# MC50_BLE.net
KiCad netlist of a schematic drawn in Altium Designer
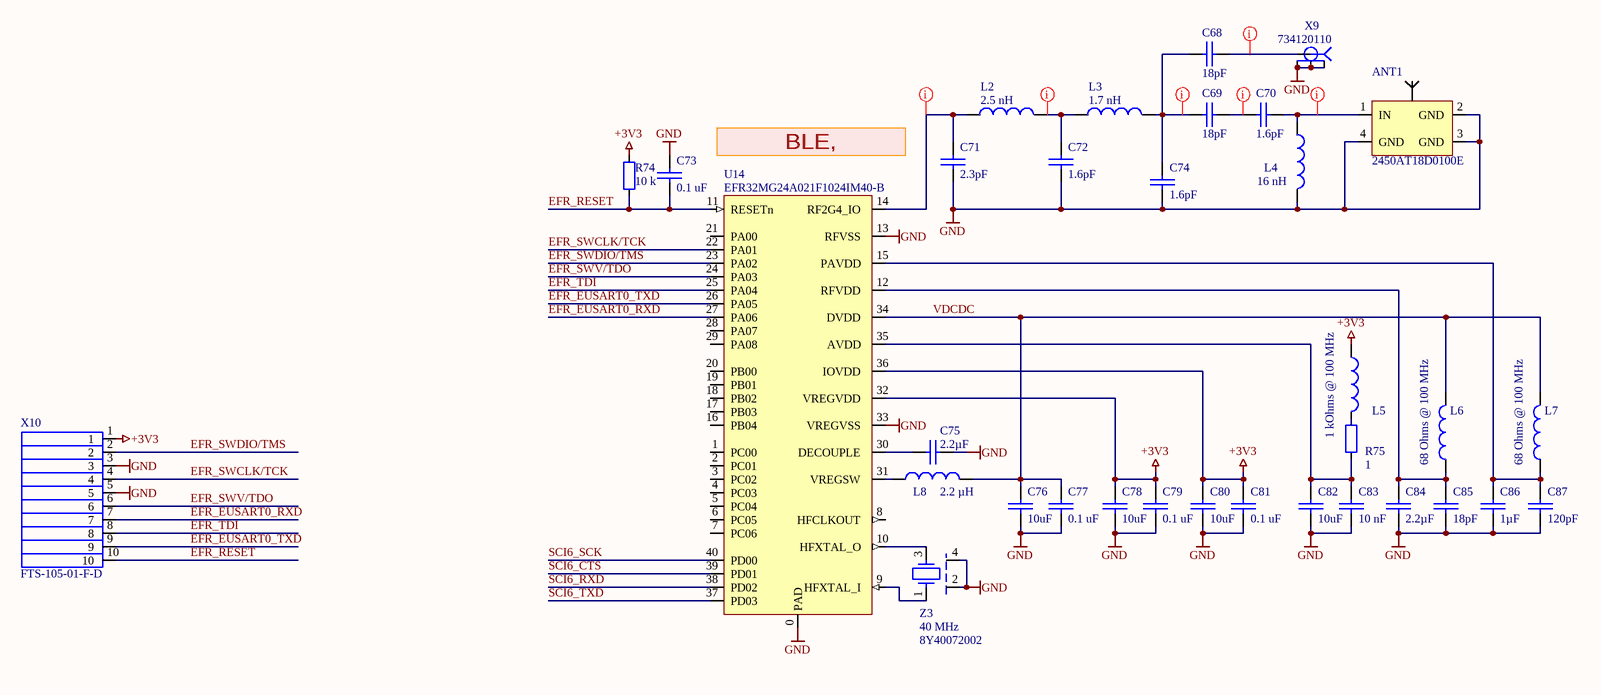
[diagram p0: MC50_BLE.SchDoc]

(export (version "E")
  (design (tool "Eeschema 10.0.6"))
  (components
    (comp (ref "ANT1")
      (value "2450AT18D0100E")
      (footprint "2450AT18D0100E_JOT")
      (description "2.4GHz Chip RF Antenna 2.4GHz ~ 2.5GHz 1.5dBi Solder Surface Mount")
      (fields
        (field (name "PARTNUM") "712-1573-1-ND")
        (field (name "MANUFACTURER") "Johanson Technology Inc.")
      )
      (libsource (lib "ea_Antennas") (part "2450AT18D0100E"))
    )
    (comp (ref "C68")
      (value "18pF")
      (footprint "0402 CAP")
      (description "18pF, ±5%, 50V, C0G, NP0, 0402 (1005 Metric), -55°C ~ 125°C, -, General Purpose")
      (fields (field (name "PART NUMBER") "CC0402JRNPO9BN180") (field (name "MANUFACTURER") "Yageo"))
      (libsource (lib "ea_PassivComps") (part "Capacitor"))
    )
    (comp (ref "C69")
      (value "18pF")
      (footprint "0402 CAP")
      (description "18pF, ±5%, 50V, C0G, NP0, 0402 (1005 Metric), -55°C ~ 125°C, -, General Purpose")
      (fields (field (name "PART NUMBER") "CC0402JRNPO9BN180") (field (name "MANUFACTURER") "Yageo"))
      (libsource (lib "ea_PassivComps") (part "Capacitor"))
    )
    (comp (ref "C70")
      (value "1.6pF")
      (footprint "0402 CAP")
      (description "1.6pF, ±0.1pF, 50V, C0G, NP0, 0402 (1005 Metric), -55°C ~ 125°C, -, General Purpose")
      (fields (field (name "PART NUMBER") "CC0402BRNPO9BN1R6") (field (name "MANUFACTURER") "Yageo"))
      (libsource (lib "ea_PassivComps") (part "Capacitor"))
    )
    (comp (ref "C71")
      (value "2.3pF")
      (footprint "0402 CAP")
      (description "2.3pF, ±0.05pF, 50V, C0G, NP0, 0402 (1005 Metric), -55°C ~ 125°C, -, RF, Microwave, High Frequency")
      (fields
        (field (name "PART NUMBER") "885392005009")
        (field (name "MANUFACTURER") "Wurth Electronics Inc.")
      )
      (libsource (lib "ea_PassivComps") (part "Capacitor"))
    )
    (comp (ref "C72")
      (value "1.6pF")
      (footprint "0402 CAP")
      (description "1.6pF, ±0.1pF, 50V, C0G, NP0, 0402 (1005 Metric), -55°C ~ 125°C, -, General Purpose")
      (fields (field (name "PART NUMBER") "CC0402BRNPO9BN1R6") (field (name "MANUFACTURER") "Yageo"))
      (libsource (lib "ea_PassivComps") (part "Capacitor"))
    )
    (comp (ref "C73")
      (value "0.1 uF")
      (footprint "1608[0603]")
      (description "0.1 µF ±10% 50V Ceramic Capacitor X7R 0603 (1608 Metric),  \r\n-55°C ~ 125°C")
      (fields
        (field (name "TOLERANCE") "+-10%")
        (field (name "MANUFACTURER") "Walsin Technology Corporation")
      )
      (libsource (lib "ea_Capacitors_0603") (part "0603B104K500CT"))
    )
    (comp (ref "C74")
      (value "1.6pF")
      (footprint "0402 CAP")
      (description "1.6pF, ±0.1pF, 50V, C0G, NP0, 0402 (1005 Metric), -55°C ~ 125°C, -, General Purpose")
      (fields (field (name "PART NUMBER") "CC0402BRNPO9BN1R6") (field (name "MANUFACTURER") "Yageo"))
      (libsource (lib "ea_PassivComps") (part "Capacitor"))
    )
    (comp (ref "C75")
      (value "2.2µF")
      (footprint "0603 CAP")
      (description "2.2µF, ±10%, 10V, X7R, 0603 (1608 Metric), -55°C ~ 125°C, -, General Purpose")
      (fields
        (field (name "PART NUMBER") "GRM188R71A225KE15D")
        (field (name "MANUFACTURER") "Murata Electronics North America")
      )
      (libsource (lib "ea_PassivComps") (part "Capacitor"))
    )
    (comp (ref "C76")
      (value "10uF")
      (footprint "1608[0603]")
      (description "10 µF ±10% 25V Ceramic Capacitor X5R 0603 (1608 Metric), -55°C ~ 85°C")
      (fields (field (name "MANUFACTURER") "Murata Electronics") (field (name "TOLERANCE") "±10%"))
      (libsource (lib "ea_Capacitors_0603") (part "GRM188R61E106KA73D"))
    )
    (comp (ref "C77")
      (value "0.1 uF")
      (footprint "1608[0603]")
      (description "0.1 µF ±10% 50V Ceramic Capacitor X7R 0603 (1608 Metric),  \r\n-55°C ~ 125°C")
      (fields
        (field (name "TOLERANCE") "+-10%")
        (field (name "MANUFACTURER") "Walsin Technology Corporation")
      )
      (libsource (lib "ea_Capacitors_0603") (part "0603B104K500CT"))
    )
    (comp (ref "C78")
      (value "10uF")
      (footprint "1608[0603]")
      (description "10 µF ±10% 25V Ceramic Capacitor X5R 0603 (1608 Metric), -55°C ~ 85°C")
      (fields (field (name "MANUFACTURER") "Murata Electronics") (field (name "TOLERANCE") "±10%"))
      (libsource (lib "ea_Capacitors_0603") (part "GRM188R61E106KA73D"))
    )
    (comp (ref "C79")
      (value "0.1 uF")
      (footprint "1608[0603]")
      (description "0.1 µF ±10% 50V Ceramic Capacitor X7R 0603 (1608 Metric),  \r\n-55°C ~ 125°C")
      (fields
        (field (name "TOLERANCE") "+-10%")
        (field (name "MANUFACTURER") "Walsin Technology Corporation")
      )
      (libsource (lib "ea_Capacitors_0603") (part "0603B104K500CT"))
    )
    (comp (ref "C80")
      (value "10uF")
      (footprint "1608[0603]")
      (description "10 µF ±10% 25V Ceramic Capacitor X5R 0603 (1608 Metric), -55°C ~ 85°C")
      (fields (field (name "MANUFACTURER") "Murata Electronics") (field (name "TOLERANCE") "±10%"))
      (libsource (lib "ea_Capacitors_0603") (part "GRM188R61E106KA73D"))
    )
    (comp (ref "C81")
      (value "0.1 uF")
      (footprint "1608[0603]")
      (description "0.1 µF ±10% 50V Ceramic Capacitor X7R 0603 (1608 Metric),  \r\n-55°C ~ 125°C")
      (fields
        (field (name "TOLERANCE") "+-10%")
        (field (name "MANUFACTURER") "Walsin Technology Corporation")
      )
      (libsource (lib "ea_Capacitors_0603") (part "0603B104K500CT"))
    )
    (comp (ref "C82")
      (value "10uF")
      (footprint "1608[0603]")
      (description "10 µF ±10% 25V Ceramic Capacitor X5R 0603 (1608 Metric), -55°C ~ 85°C")
      (fields (field (name "MANUFACTURER") "Murata Electronics") (field (name "TOLERANCE") "±10%"))
      (libsource (lib "ea_Capacitors_0603") (part "GRM188R61E106KA73D"))
    )
    (comp (ref "C83")
      (value "10 nF")
      (footprint "0603 CAP")
      (description "10000pF, ±5%, 50V, C0G, NP0, 0603 (1608 Metric), -55°C ~ 125°C, Low ESL, General Purpose")
      (fields
        (field (name "PART NUMBER") "C1608C0G1H103J080AA")
        (field (name "MANUFACTURER") "TDK Corporation")
      )
      (libsource (lib "ea_PassivComps") (part "Capacitor"))
    )
    (comp (ref "C84")
      (value "2.2µF")
      (footprint "0603 CAP")
      (description "2.2µF, ±10%, 10V, X7R, 0603 (1608 Metric), -55°C ~ 125°C, -, General Purpose")
      (fields
        (field (name "PART NUMBER") "GRM188R71A225KE15D")
        (field (name "MANUFACTURER") "Murata Electronics North America")
      )
      (libsource (lib "ea_PassivComps") (part "Capacitor"))
    )
    (comp (ref "C85")
      (value "18pF")
      (footprint "0603 CAP")
      (description "18pF, ±10%, 50V, C0G, NP0, 0603 (1608 Metric), -55°C ~ 125°C, Low ESL, General Purpose")
      (fields (field (name "PART NUMBER") "C0603C180K5GACTU") (field (name "MANUFACTURER") "KEMET"))
      (libsource (lib "ea_PassivComps") (part "Capacitor"))
    )
    (comp (ref "C86")
      (value "1µF")
      (footprint "0603 CAP")
      (description "1µF, ±10%, 50V, X5R, 0603 (1608 Metric), -55°C ~ 85°C, -, General Purpose")
      (fields
        (field (name "PART NUMBER") "CL10A105KB8NNNC")
        (field (name "MANUFACTURER") "Samsung Electro-Mechanics")
      )
      (libsource (lib "ea_PassivComps") (part "Capacitor"))
    )
    (comp (ref "C87")
      (value "120pF")
      (footprint "0603 CAP")
      (description "120pF, ±5%, 50V, C0G, NP0, 0603 (1608 Metric), -55°C ~ 125°C, -, General Purpose")
      (fields
        (field (name "PART NUMBER") "CL10C121JB8NCNC")
        (field (name "MANUFACTURER") "Samsung Electro-Mechanics")
      )
      (libsource (lib "ea_PassivComps") (part "Capacitor"))
    )
    (comp (ref "L2")
      (value "2.5 nH")
      (footprint "INDC1005-0402")
      (description "2.5 nH Unshielded Thin Film Inductor 440 mA 350mOhm Max 0402 (1005 Metric)")
      (fields (field (name "MANUFACTURER") "Abracon LLC") (field (name "TOLERANCE") "±0.1nH"))
      (libsource (lib "ea_RF_inductors") (part "ATFC-0402-2N5B-T"))
    )
    (comp (ref "L3")
      (value "1.7 nH")
      (footprint "INDC1005-0402")
      (description "1.7 nH Unshielded Thin Film Inductor 560 mA 250mOhm Max 0402 (1005 Metric)")
      (fields (field (name "MANUFACTURER") "Abracon LLC") (field (name "TOLERANCE") "±0.1nH"))
      (libsource (lib "ea_RF_inductors") (part "ATFC-0402-1N7B-T"))
    )
    (comp (ref "L4")
      (value "16 nH")
      (footprint "INDC1005-0402")
      (description "16 nH Unshielded Drum Core, Wirewound Inductor 850 mA 130mOhm 0402 (1005 Metric)")
      (fields (field (name "MANUFACTURER") "Delta Electronics/Components") (field (name "TOLERANCE") "5%"))
      (libsource (lib "ea_RF_inductors") (part "0402HP-160EJTS"))
    )
    (comp (ref "L5")
      (value "1 kOhms @ 100 MHz")
      (footprint "0603")
      (description "1 kOhms @ 100 MHz 1 Power, Signal Line Ferrite Bead 0603 (1608 Metric) 200mA 600mOhm")
      (fields
        (field (name "MANUFACTURER") "Laird-Signal Integrity Products")
        (field (name "PARTNUM") "240-2378-1-ND")
      )
      (libsource (lib "ea_Inductors") (part "HZ0603B102R-10"))
    )
    (comp (ref "L6")
      (value "68 Ohms @ 100 MHz")
      (footprint "0603")
      (description "68 Ohms @ 100 MHz 1 Ferrite Bead 0603 (1608 Metric) 200mA 100mOhm, -55°C ~ 125°C")
      (fields (field (name "MANUFACTURER") "Murata Manufacturing") (field (name "PARTNUM") "541-2605-1-ND"))
      (libsource (lib "ea_Inductors") (part "ILBB0603ER680V"))
    )
    (comp (ref "L7")
      (value "68 Ohms @ 100 MHz")
      (footprint "0603")
      (description "68 Ohms @ 100 MHz 1 Ferrite Bead 0603 (1608 Metric) 200mA 100mOhm, -55°C ~ 125°C")
      (fields (field (name "MANUFACTURER") "Murata Manufacturing") (field (name "PARTNUM") "541-2605-1-ND"))
      (libsource (lib "ea_Inductors") (part "ILBB0603ER680V"))
    )
    (comp (ref "L8")
      (value "2.2 µH")
      (footprint "0603")
      (description "2.2 µH Shielded Multilayer Inductor 700 mA 470mOhm Max 0603 (1608 Metric)")
      (fields (field (name "MANUFACTURER") "Murata Electronics") (field (name "PARTNUM") "490-15982-1-ND"))
      (libsource (lib "ea_Inductors") (part "LQM18PZ2R2MFHD"))
    )
    (comp (ref "R74")
      (value "10 k")
      (footprint "0603")
      (fields
        (field (name "MANUFACTURER") "Bourns Inc.")
        (field (name "TOLERANCE") "±1%")
        (field (name "VOLTAGE") "75V")
      )
      (libsource (lib "") (part "Resistor_1"))
    )
    (comp (ref "R75")
      (value "1")
      (footprint "0603")
      (description "1 Ohms, ±1%, 0.1W, 1/10W, Thick Film, ±100ppm/°C, 0603 (1608 Metric), -55°C ~ 155°C, -")
      (fields (field (name "MANUFACTURER") "Vishay Dale") (field (name "TOLERANCE") "±1%"))
      (libsource (lib "ea_PassivComps") (part "Resistor"))
    )
    (comp (ref "U14")
      (value "EFR32MG24A021F1024IM40-B")
      (footprint "QFN40 Silabs")
      (fields
        (field (name "MANUFACTURER") "Silicon Labs")
        (field (name "PARTNUM") "336-EFR32MG24A021F1024IM40-B-ND")
      )
      (libsource (lib "ea_IC_RF") (part "EFR32MG24A021F1024IM40-B"))
    )
    (comp (ref "X9")
      (value "734120110")
      (footprint "0734120110")
      (description "U.FL (UMCC) Connector Receptacle, Male Pin 50 Ohm Surface Mount Solder")
      (fields (field (name "MANUFACTURER") "Molex") (field (name "PARTNUM") "WM5587TR-ND"))
      (libsource (lib "ea_Connectors_RF") (part "0734120110"))
    )
    (comp (ref "X10")
      (value "FTS-105-01-F-D")
      (footprint "FTS-105-01-F-D")
      (description "Board-To-Board Connector, Vertical, FTS Series, Through Hole, Header, 10, 1.27 mm")
      (fields (field (name "MANUFACTURER") "SAMTEC") (field (name "PARTNUM") "1928242"))
      (libsource (lib "ea_JTAG_SWD") (part "FTS-105-01-F-D"))
    )
    (comp (ref "Z3")
      (value "8Y40072002")
      (footprint "4-SMD 2.00mm x 1.60mm")
      (description "40 MHz Crystal 8pF 80 Ohms 4-SMD, No Lead, -20°C ~ 70°C")
      (fields
        (field (name "MANUFACTURER") "TXC CORPORATION")
        (field (name "PARTNUM") "887-8Y40072002CT-ND")
        (field (name "ALTIUM_VALUE") "40 MHz")
      )
      (libsource (lib "ea_OSC_CLK_GEN") (part "8Y40072002"))
    )
  )
  (nets
    (net (code "1") (name "+3V3") (class "Default")
      (node (ref "C78") (pin "1") (pinfunction "1_1") (pintype "passive"))
      (node (ref "C79") (pin "2") (pinfunction "2_2") (pintype "passive"))
      (node (ref "C80") (pin "1") (pinfunction "1_1") (pintype "passive"))
      (node (ref "C81") (pin "2") (pinfunction "2_2") (pintype "passive"))
      (node (ref "L5") (pin "1") (pinfunction "1_1") (pintype "passive"))
      (node (ref "R74") (pin "1") (pinfunction "1_1") (pintype "passive"))
      (node (ref "U14") (pin "32") (pinfunction "VREGVDD_32") (pintype "power_in"))
      (node (ref "U14") (pin "36") (pinfunction "IOVDD_36") (pintype "power_in"))
      (node (ref "X10") (pin "1") (pinfunction "1_1") (pintype "passive"))
    )
    (net (code "2") (name "/EFR_EUSART0_RXD") (class "Default")
      (node (ref "U14") (pin "27") (pinfunction "PA06_27") (pintype "bidirectional"))
      (node (ref "X10") (pin "7") (pinfunction "7_7") (pintype "power_in"))
    )
    (net (code "3") (name "/EFR_EUSART0_TXD") (class "Default")
      (node (ref "U14") (pin "26") (pinfunction "PA05_26") (pintype "bidirectional"))
      (node (ref "X10") (pin "9") (pinfunction "9_9") (pintype "power_in"))
    )
    (net (code "4") (name "/EFR_RESET") (class "Default")
      (node (ref "C73") (pin "1") (pinfunction "1_1") (pintype "passive"))
      (node (ref "R74") (pin "2") (pinfunction "2_2") (pintype "passive"))
      (node (ref "U14") (pin "11") (pinfunction "RESETn_11") (pintype "input"))
      (node (ref "X10") (pin "10") (pinfunction "10_10") (pintype "power_in"))
    )
    (net (code "5") (name "/EFR_SWCLK{slash}TCK") (class "Default")
      (node (ref "U14") (pin "22") (pinfunction "PA01_22") (pintype "bidirectional"))
      (node (ref "X10") (pin "4") (pinfunction "4_4") (pintype "passive"))
    )
    (net (code "6") (name "/EFR_SWDIO{slash}TMS") (class "Default")
      (node (ref "U14") (pin "23") (pinfunction "PA02_23") (pintype "bidirectional"))
      (node (ref "X10") (pin "2") (pinfunction "2_2") (pintype "passive"))
    )
    (net (code "7") (name "/EFR_SWV{slash}TDO") (class "Default")
      (node (ref "U14") (pin "24") (pinfunction "PA03_24") (pintype "bidirectional"))
      (node (ref "X10") (pin "6") (pinfunction "6_6") (pintype "power_in"))
    )
    (net (code "8") (name "/EFR_TDI") (class "Default")
      (node (ref "U14") (pin "25") (pinfunction "PA04_25") (pintype "bidirectional"))
      (node (ref "X10") (pin "8") (pinfunction "8_8") (pintype "power_in"))
    )
    (net (code "9") (name "/SCI6_CTS") (class "Default")
      (node (ref "U14") (pin "39") (pinfunction "PD01_39") (pintype "bidirectional"))
    )
    (net (code "10") (name "/SCI6_RXD") (class "Default")
      (node (ref "U14") (pin "38") (pinfunction "PD02_38") (pintype "bidirectional"))
    )
    (net (code "11") (name "/SCI6_SCK") (class "Default")
      (node (ref "U14") (pin "40") (pinfunction "PD00_40") (pintype "bidirectional"))
    )
    (net (code "12") (name "/SCI6_TXD") (class "Default")
      (node (ref "U14") (pin "37") (pinfunction "PD03_37") (pintype "bidirectional"))
    )
    (net (code "13") (name "/VDCDC") (class "Default")
      (node (ref "C76") (pin "1") (pinfunction "1_1") (pintype "passive"))
      (node (ref "C77") (pin "2") (pinfunction "2_2") (pintype "passive"))
      (node (ref "L6") (pin "2") (pinfunction "2_2") (pintype "passive"))
      (node (ref "L7") (pin "2") (pinfunction "2_2") (pintype "passive"))
      (node (ref "L8") (pin "2") (pinfunction "2_2") (pintype "passive"))
      (node (ref "U14") (pin "34") (pinfunction "DVDD_34") (pintype "power_in"))
    )
    (net (code "14") (name "GND") (class "Default")
      (node (ref "ANT1") (pin "2") (pinfunction "GND_2") (pintype "passive"))
      (node (ref "ANT1") (pin "3") (pinfunction "GND_3") (pintype "passive"))
      (node (ref "ANT1") (pin "4") (pinfunction "GND_4") (pintype "passive"))
      (node (ref "C71") (pin "2") (pinfunction "2_2") (pintype "passive"))
      (node (ref "C72") (pin "2") (pinfunction "2_2") (pintype "passive"))
      (node (ref "C73") (pin "2") (pinfunction "2_2") (pintype "passive"))
      (node (ref "C74") (pin "2") (pinfunction "2_2") (pintype "passive"))
      (node (ref "C75") (pin "2") (pinfunction "2_2") (pintype "passive"))
      (node (ref "C76") (pin "2") (pinfunction "2_2") (pintype "passive"))
      (node (ref "C77") (pin "1") (pinfunction "1_1") (pintype "passive"))
      (node (ref "C78") (pin "2") (pinfunction "2_2") (pintype "passive"))
      (node (ref "C79") (pin "1") (pinfunction "1_1") (pintype "passive"))
      (node (ref "C80") (pin "2") (pinfunction "2_2") (pintype "passive"))
      (node (ref "C81") (pin "1") (pinfunction "1_1") (pintype "passive"))
      (node (ref "C82") (pin "2") (pinfunction "2_2") (pintype "passive"))
      (node (ref "C83") (pin "2") (pinfunction "2_2") (pintype "passive"))
      (node (ref "C84") (pin "1") (pinfunction "1_1") (pintype "passive"))
      (node (ref "C85") (pin "2") (pinfunction "2_2") (pintype "passive"))
      (node (ref "C86") (pin "2") (pinfunction "2_2") (pintype "passive"))
      (node (ref "C87") (pin "2") (pinfunction "2_2") (pintype "passive"))
      (node (ref "L4") (pin "2") (pinfunction "2_2") (pintype "passive"))
      (node (ref "U14") (pin "0") (pinfunction "PAD_0") (pintype "power_in"))
      (node (ref "U14") (pin "13") (pinfunction "RFVSS_13") (pintype "power_in"))
      (node (ref "U14") (pin "33") (pinfunction "VREGVSS_33") (pintype "power_in"))
      (node (ref "X10") (pin "3") (pinfunction "3_3") (pintype "passive"))
      (node (ref "X10") (pin "5") (pinfunction "5_5") (pintype "power_in"))
      (node (ref "X9") (pin "2") (pinfunction "2_2") (pintype "passive"))
      (node (ref "X9") (pin "3") (pinfunction "3_3") (pintype "passive"))
      (node (ref "X9") (pin "4") (pinfunction "3_4") (pintype "passive"))
      (node (ref "Z3") (pin "2") (pinfunction "2_2") (pintype "passive"))
      (node (ref "Z3") (pin "4") (pinfunction "4_4") (pintype "passive"))
    )
    (net (code "15") (name "Net-(ANT1-IN)") (class "Default")
      (node (ref "ANT1") (pin "1") (pinfunction "IN_1") (pintype "passive"))
      (node (ref "C70") (pin "2") (pinfunction "2_2") (pintype "passive"))
      (node (ref "L4") (pin "1") (pinfunction "1_1") (pintype "passive"))
    )
    (net (code "16") (name "Net-(C68-Pad1)") (class "Default")
      (node (ref "C68") (pin "1") (pinfunction "1_1") (pintype "passive"))
      (node (ref "C69") (pin "1") (pinfunction "1_1") (pintype "passive"))
      (node (ref "C74") (pin "1") (pinfunction "1_1") (pintype "passive"))
      (node (ref "L3") (pin "2") (pinfunction "2_2") (pintype "passive"))
    )
    (net (code "17") (name "Net-(C69-Pad2)") (class "Default")
      (node (ref "C69") (pin "2") (pinfunction "2_2") (pintype "passive"))
      (node (ref "C70") (pin "1") (pinfunction "1_1") (pintype "passive"))
    )
    (net (code "18") (name "Net-(C72-Pad1)") (class "Default")
      (node (ref "C72") (pin "1") (pinfunction "1_1") (pintype "passive"))
      (node (ref "L2") (pin "2") (pinfunction "2_2") (pintype "passive"))
      (node (ref "L3") (pin "1") (pinfunction "1_1") (pintype "passive"))
    )
    (net (code "19") (name "Net-(L5-Pad2)") (class "Default")
      (node (ref "L5") (pin "2") (pinfunction "2_2") (pintype "passive"))
      (node (ref "R75") (pin "2") (pinfunction "2_2") (pintype "passive"))
    )
    (net (code "20") (name "Net-(U14-AVDD)") (class "Default")
      (node (ref "C82") (pin "1") (pinfunction "1_1") (pintype "passive"))
      (node (ref "C83") (pin "1") (pinfunction "1_1") (pintype "passive"))
      (node (ref "R75") (pin "1") (pinfunction "1_1") (pintype "passive"))
      (node (ref "U14") (pin "35") (pinfunction "AVDD_35") (pintype "power_in"))
    )
    (net (code "21") (name "Net-(U14-DECOUPLE)") (class "Default")
      (node (ref "C75") (pin "1") (pinfunction "1_1") (pintype "passive"))
      (node (ref "U14") (pin "30") (pinfunction "DECOUPLE_30") (pintype "bidirectional"))
    )
    (net (code "22") (name "Net-(U14-HFXTAL_I)") (class "Default")
      (node (ref "U14") (pin "9") (pinfunction "HFXTAL_I_9") (pintype "input"))
      (node (ref "Z3") (pin "1") (pinfunction "1_1") (pintype "passive"))
    )
    (net (code "23") (name "Net-(U14-HFXTAL_O)") (class "Default")
      (node (ref "U14") (pin "10") (pinfunction "HFXTAL_O_10") (pintype "output"))
      (node (ref "Z3") (pin "3") (pinfunction "3_3") (pintype "passive"))
    )
    (net (code "24") (name "Net-(U14-PAVDD)") (class "Default")
      (node (ref "C86") (pin "1") (pinfunction "1_1") (pintype "passive"))
      (node (ref "C87") (pin "1") (pinfunction "1_1") (pintype "passive"))
      (node (ref "L7") (pin "1") (pinfunction "1_1") (pintype "passive"))
      (node (ref "U14") (pin "15") (pinfunction "PAVDD_15") (pintype "power_in"))
    )
    (net (code "25") (name "Net-(U14-RF2G4_IO)") (class "Default")
      (node (ref "C71") (pin "1") (pinfunction "1_1") (pintype "passive"))
      (node (ref "L2") (pin "1") (pinfunction "1_1") (pintype "passive"))
      (node (ref "U14") (pin "14") (pinfunction "RF2G4_IO_14") (pintype "bidirectional"))
    )
    (net (code "26") (name "Net-(U14-RFVDD)") (class "Default")
      (node (ref "C84") (pin "2") (pinfunction "2_2") (pintype "passive"))
      (node (ref "C85") (pin "1") (pinfunction "1_1") (pintype "passive"))
      (node (ref "L6") (pin "1") (pinfunction "1_1") (pintype "passive"))
      (node (ref "U14") (pin "12") (pinfunction "RFVDD_12") (pintype "power_in"))
    )
    (net (code "27") (name "Net-(U14-VREGSW)") (class "Default")
      (node (ref "L8") (pin "1") (pinfunction "1_1") (pintype "passive"))
      (node (ref "U14") (pin "31") (pinfunction "VREGSW_31") (pintype "bidirectional"))
    )
    (net (code "28") (name "Net-(X9-Sig)") (class "Default")
      (node (ref "C68") (pin "2") (pinfunction "2_2") (pintype "passive"))
      (node (ref "X9") (pin "1") (pinfunction "Sig_1") (pintype "passive"))
    )
    (net (code "29") (name "unconnected-(U14-HFCLKOUT-Pad8)") (class "Default")
      (node (ref "U14") (pin "8") (pinfunction "HFCLKOUT_8") (pintype "output"))
    )
    (net (code "30") (name "unconnected-(U14-PA00-Pad21)") (class "Default")
      (node (ref "U14") (pin "21") (pinfunction "PA00_21") (pintype "bidirectional"))
    )
    (net (code "31") (name "unconnected-(U14-PA07-Pad28)") (class "Default")
      (node (ref "U14") (pin "28") (pinfunction "PA07_28") (pintype "bidirectional"))
    )
    (net (code "32") (name "unconnected-(U14-PA08-Pad29)") (class "Default")
      (node (ref "U14") (pin "29") (pinfunction "PA08_29") (pintype "bidirectional"))
    )
    (net (code "33") (name "unconnected-(U14-PB00-Pad20)") (class "Default")
      (node (ref "U14") (pin "20") (pinfunction "PB00_20") (pintype "bidirectional"))
    )
    (net (code "34") (name "unconnected-(U14-PB01-Pad19)") (class "Default")
      (node (ref "U14") (pin "19") (pinfunction "PB01_19") (pintype "bidirectional"))
    )
    (net (code "35") (name "unconnected-(U14-PB02-Pad18)") (class "Default")
      (node (ref "U14") (pin "18") (pinfunction "PB02_18") (pintype "bidirectional"))
    )
    (net (code "36") (name "unconnected-(U14-PB03-Pad17)") (class "Default")
      (node (ref "U14") (pin "17") (pinfunction "PB03_17") (pintype "bidirectional"))
    )
    (net (code "37") (name "unconnected-(U14-PB04-Pad16)") (class "Default")
      (node (ref "U14") (pin "16") (pinfunction "PB04_16") (pintype "bidirectional"))
    )
    (net (code "38") (name "unconnected-(U14-PC00-Pad1)") (class "Default")
      (node (ref "U14") (pin "1") (pinfunction "PC00_1") (pintype "bidirectional"))
    )
    (net (code "39") (name "unconnected-(U14-PC01-Pad2)") (class "Default")
      (node (ref "U14") (pin "2") (pinfunction "PC01_2") (pintype "bidirectional"))
    )
    (net (code "40") (name "unconnected-(U14-PC02-Pad3)") (class "Default")
      (node (ref "U14") (pin "3") (pinfunction "PC02_3") (pintype "bidirectional"))
    )
    (net (code "41") (name "unconnected-(U14-PC03-Pad4)") (class "Default")
      (node (ref "U14") (pin "4") (pinfunction "PC03_4") (pintype "bidirectional"))
    )
    (net (code "42") (name "unconnected-(U14-PC04-Pad5)") (class "Default")
      (node (ref "U14") (pin "5") (pinfunction "PC04_5") (pintype "bidirectional"))
    )
    (net (code "43") (name "unconnected-(U14-PC05-Pad6)") (class "Default")
      (node (ref "U14") (pin "6") (pinfunction "PC05_6") (pintype "bidirectional"))
    )
    (net (code "44") (name "unconnected-(U14-PC06-Pad7)") (class "Default")
      (node (ref "U14") (pin "7") (pinfunction "PC06_7") (pintype "bidirectional"))
    )
  )
)
